# FIT_TCM_SI5338A.net
KiCad netlist of a schematic drawn in Altium Designer
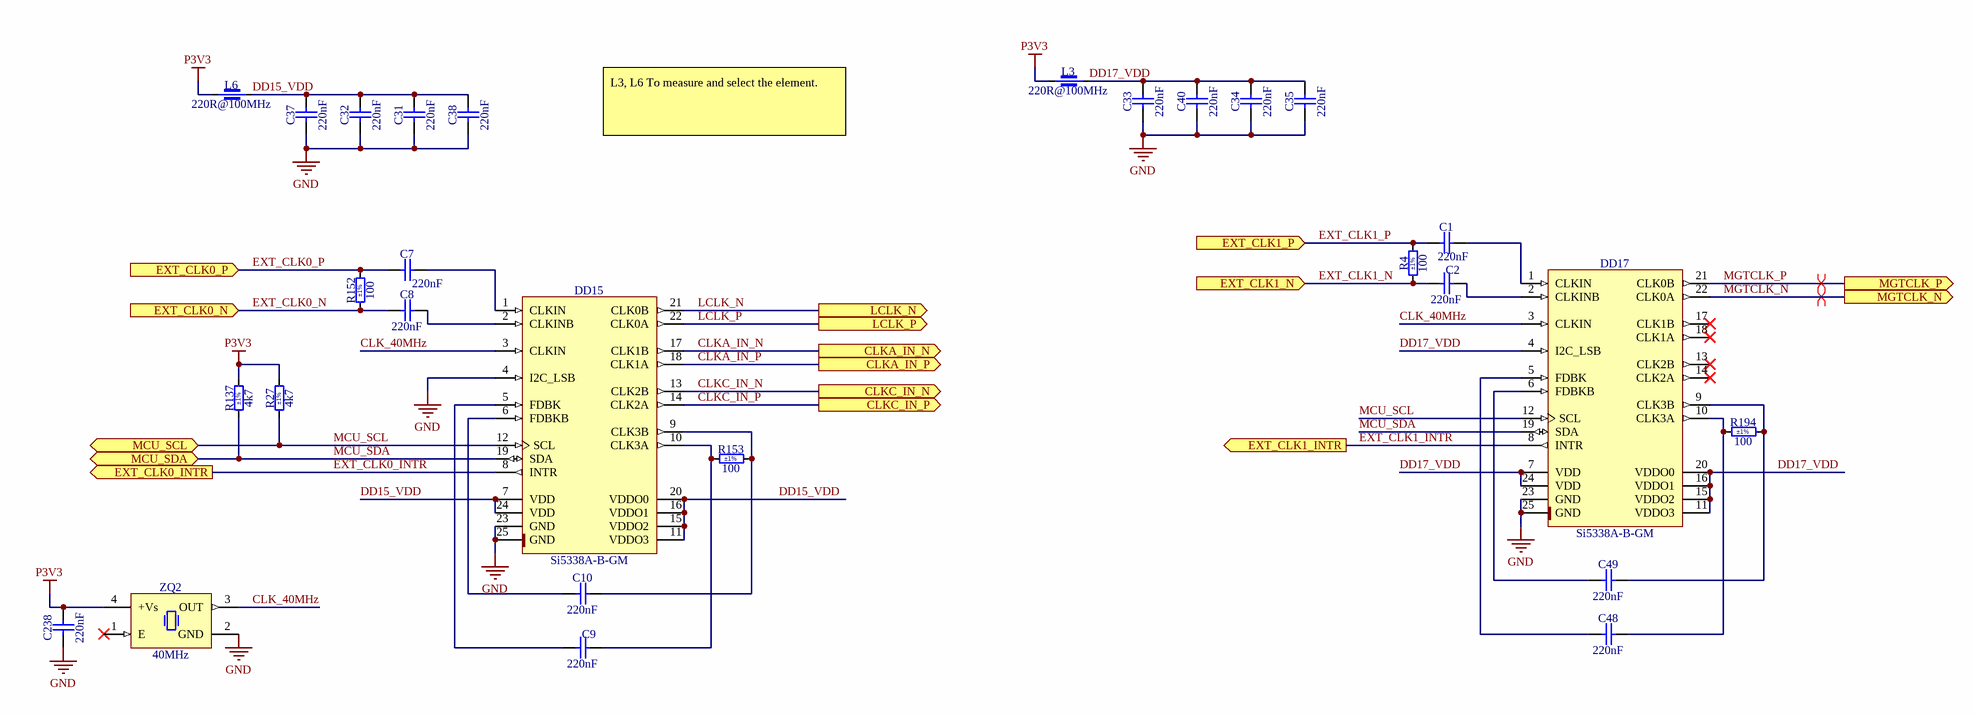
[diagram p0: FIT_TCM_SI5338A.SchDoc]

(export (version "E")
  (design (tool "Eeschema 10.0.6"))
  (components
    (comp (ref "C1")
      (value "220nF")
      (footprint "CAPC1608X87N")
      (description "Non-polarised capacitor")
      (fields
        (field (name "PART NUMBER") "CC0603_220NF_25V_10%_X7R")
        (field (name "VOLTAGE") "25V")
        (field (name "AUTHOR") "CERN DEM JLC")
      )
      (libsource (lib "Capacitors") (part "Capacitor - non polarized"))
    )
    (comp (ref "C2")
      (value "220nF")
      (footprint "CAPC1608X87N")
      (description "Non-polarised capacitor")
      (fields
        (field (name "PART NUMBER") "CC0603_220NF_25V_10%_X7R")
        (field (name "VOLTAGE") "25V")
        (field (name "AUTHOR") "CERN DEM JLC")
      )
      (libsource (lib "Capacitors") (part "Capacitor - non polarized"))
    )
    (comp (ref "C7")
      (value "220nF")
      (footprint "CAPC1608X87N")
      (description "Non-polarised capacitor")
      (fields
        (field (name "PART NUMBER") "CC0603_220NF_25V_10%_X7R")
        (field (name "VOLTAGE") "25V")
        (field (name "AUTHOR") "CERN DEM JLC")
      )
      (libsource (lib "Capacitors") (part "Capacitor - non polarized"))
    )
    (comp (ref "C8")
      (value "220nF")
      (footprint "CAPC1608X87N")
      (description "Non-polarised capacitor")
      (fields
        (field (name "PART NUMBER") "CC0603_220NF_25V_10%_X7R")
        (field (name "VOLTAGE") "25V")
        (field (name "AUTHOR") "CERN DEM JLC")
      )
      (libsource (lib "Capacitors") (part "Capacitor - non polarized"))
    )
    (comp (ref "C9")
      (value "220nF")
      (footprint "CAPC1608X87N")
      (description "Non-polarised capacitor")
      (fields
        (field (name "PART NUMBER") "CC0603_220NF_25V_10%_X7R")
        (field (name "VOLTAGE") "25V")
        (field (name "AUTHOR") "CERN DEM JLC")
      )
      (libsource (lib "Capacitors") (part "Capacitor - non polarized"))
    )
    (comp (ref "C10")
      (value "220nF")
      (footprint "CAPC1608X87N")
      (description "Non-polarised capacitor")
      (fields
        (field (name "PART NUMBER") "CC0603_220NF_25V_10%_X7R")
        (field (name "VOLTAGE") "25V")
        (field (name "AUTHOR") "CERN DEM JLC")
      )
      (libsource (lib "Capacitors") (part "Capacitor - non polarized"))
    )
    (comp (ref "C31")
      (value "220nF")
      (footprint "CAPC2012X135N")
      (description "Non-polarised capacitor")
      (fields
        (field (name "PART NUMBER") "CC0805_220NF_50V_10%_X7R")
        (field (name "VOLTAGE") "50V")
        (field (name "AUTHOR") "CERN DEM JLC")
      )
      (libsource (lib "Capacitors") (part "Capacitor - non polarized"))
    )
    (comp (ref "C32")
      (value "220nF")
      (footprint "CAPC2012X135N")
      (description "Non-polarised capacitor")
      (fields
        (field (name "PART NUMBER") "CC0805_220NF_50V_10%_X7R")
        (field (name "VOLTAGE") "50V")
        (field (name "AUTHOR") "CERN DEM JLC")
      )
      (libsource (lib "Capacitors") (part "Capacitor - non polarized"))
    )
    (comp (ref "C33")
      (value "220nF")
      (footprint "CAPC2012X135N")
      (description "Non-polarised capacitor")
      (fields
        (field (name "PART NUMBER") "CC0805_220NF_50V_10%_X7R")
        (field (name "VOLTAGE") "50V")
        (field (name "AUTHOR") "CERN DEM JLC")
      )
      (libsource (lib "Capacitors") (part "Capacitor - non polarized"))
    )
    (comp (ref "C34")
      (value "220nF")
      (footprint "CAPC2012X135N")
      (description "Non-polarised capacitor")
      (fields
        (field (name "PART NUMBER") "CC0805_220NF_50V_10%_X7R")
        (field (name "VOLTAGE") "50V")
        (field (name "AUTHOR") "CERN DEM JLC")
      )
      (libsource (lib "Capacitors") (part "Capacitor - non polarized"))
    )
    (comp (ref "C35")
      (value "220nF")
      (footprint "CAPC2012X135N")
      (description "Non-polarised capacitor")
      (fields
        (field (name "PART NUMBER") "CC0805_220NF_50V_10%_X7R")
        (field (name "VOLTAGE") "50V")
        (field (name "AUTHOR") "CERN DEM JLC")
      )
      (libsource (lib "Capacitors") (part "Capacitor - non polarized"))
    )
    (comp (ref "C37")
      (value "220nF")
      (footprint "CAPC2012X135N")
      (description "Non-polarised capacitor")
      (fields
        (field (name "PART NUMBER") "CC0805_220NF_50V_10%_X7R")
        (field (name "VOLTAGE") "50V")
        (field (name "AUTHOR") "CERN DEM JLC")
      )
      (libsource (lib "Capacitors") (part "Capacitor - non polarized"))
    )
    (comp (ref "C38")
      (value "220nF")
      (footprint "CAPC2012X135N")
      (description "Non-polarised capacitor")
      (fields
        (field (name "PART NUMBER") "CC0805_220NF_50V_10%_X7R")
        (field (name "VOLTAGE") "50V")
        (field (name "AUTHOR") "CERN DEM JLC")
      )
      (libsource (lib "Capacitors") (part "Capacitor - non polarized"))
    )
    (comp (ref "C40")
      (value "220nF")
      (footprint "CAPC2012X135N")
      (description "Non-polarised capacitor")
      (fields
        (field (name "PART NUMBER") "CC0805_220NF_50V_10%_X7R")
        (field (name "VOLTAGE") "50V")
        (field (name "AUTHOR") "CERN DEM JLC")
      )
      (libsource (lib "Capacitors") (part "Capacitor - non polarized"))
    )
    (comp (ref "C48")
      (value "220nF")
      (footprint "CAPC1608X87N")
      (description "Non-polarised capacitor")
      (fields
        (field (name "PART NUMBER") "CC0603_220NF_25V_10%_X7R")
        (field (name "VOLTAGE") "25V")
        (field (name "AUTHOR") "CERN DEM JLC")
      )
      (libsource (lib "Capacitors") (part "Capacitor - non polarized"))
    )
    (comp (ref "C49")
      (value "220nF")
      (footprint "CAPC1608X87N")
      (description "Non-polarised capacitor")
      (fields
        (field (name "PART NUMBER") "CC0603_220NF_25V_10%_X7R")
        (field (name "VOLTAGE") "25V")
        (field (name "AUTHOR") "CERN DEM JLC")
      )
      (libsource (lib "Capacitors") (part "Capacitor - non polarized"))
    )
    (comp (ref "C238")
      (value "220nF")
      (footprint "CAPC2012X135N")
      (description "Non-polarised capacitor")
      (fields
        (field (name "PART NUMBER") "CC0805_220NF_50V_10%_X7R")
        (field (name "VOLTAGE") "50V")
        (field (name "AUTHOR") "CERN DEM JLC")
      )
      (libsource (lib "Capacitors") (part "Capacitor - non polarized"))
    )
    (comp (ref "DD15")
      (value "Si5338A-B-GM")
      (footprint "QFN50P400X400X90-25N-S265")
      (description "I2C-Programmable Any-Frequency, Any-Output Quad Clock Generator")
      (fields (field (name "MANUFACTURER") "SILICON LABS") (field (name "AUTHOR") "CERN DEM JMW"))
      (libsource (lib "ICs And Semiconductors") (part "Si5338A"))
    )
    (comp (ref "DD17")
      (value "Si5338A-B-GM")
      (footprint "QFN50P400X400X90-25N-S265")
      (description "I2C-Programmable Any-Frequency, Any-Output Quad Clock Generator")
      (fields (field (name "MANUFACTURER") "SILICON LABS") (field (name "AUTHOR") "CERN DEM JMW"))
      (libsource (lib "ICs And Semiconductors") (part "Si5338A"))
    )
    (comp (ref "L3")
      (value "220R@100MHz")
      (footprint "INDC2012X105N")
      (fields
        (field (name "PART NUMBER") "IND0805_TDK_MPZ2012S221A")
        (field (name "POWER") "3A")
        (field (name "TOLERANCE") "±25%")
        (field (name "AUTHOR") "CERN DEM HF")
      )
      (libsource (lib "Inductors & Transformers") (part "Ferrite Bead"))
    )
    (comp (ref "L6")
      (value "220R@100MHz")
      (footprint "INDC2012X105N")
      (fields
        (field (name "PART NUMBER") "IND0805_TDK_MPZ2012S221A")
        (field (name "POWER") "3A")
        (field (name "TOLERANCE") "±25%")
        (field (name "AUTHOR") "CERN DEM HF")
      )
      (libsource (lib "Inductors & Transformers") (part "Ferrite Bead"))
    )
    (comp (ref "R4")
      (value "100")
      (footprint "RESC1608X55N")
      (description "Resistor - 1%")
      (fields
        (field (name "TOLERANCE") "±1%")
        (field (name "PART NUMBER") "R0603_100R_1%_0.1W_100PPM")
        (field (name "POWER") "0.1W")
        (field (name "AUTHOR") "CERN DEM JLC")
      )
      (libsource (lib "Resistors") (part "Resistor - 1%"))
    )
    (comp (ref "R27")
      (value "4k7")
      (footprint "RESC2012X60N")
      (description "Resistor - 1%")
      (fields
        (field (name "TOLERANCE") "±1%")
        (field (name "PART NUMBER") "R0805_4K7_1%_0.125W_100PPM")
        (field (name "POWER") "0.125W")
        (field (name "AUTHOR") "CERN DEM JLC")
      )
      (libsource (lib "Resistors") (part "Resistor - 1%"))
    )
    (comp (ref "R137")
      (value "4k7")
      (footprint "RESC2012X60N")
      (description "Resistor - 1%")
      (fields
        (field (name "TOLERANCE") "±1%")
        (field (name "PART NUMBER") "R0805_4K7_1%_0.125W_100PPM")
        (field (name "POWER") "0.125W")
        (field (name "AUTHOR") "CERN DEM JLC")
      )
      (libsource (lib "Resistors") (part "Resistor - 1%"))
    )
    (comp (ref "R152")
      (value "100")
      (footprint "RESC1608X55N")
      (description "Resistor - 1%")
      (fields
        (field (name "TOLERANCE") "±1%")
        (field (name "PART NUMBER") "R0603_100R_1%_0.1W_100PPM")
        (field (name "POWER") "0.1W")
        (field (name "AUTHOR") "CERN DEM JLC")
      )
      (libsource (lib "Resistors") (part "Resistor - 1%"))
    )
    (comp (ref "R153")
      (value "100")
      (footprint "RESC1608X55N")
      (description "Resistor - 1%")
      (fields
        (field (name "TOLERANCE") "±1%")
        (field (name "PART NUMBER") "R0603_100R_1%_0.1W_100PPM")
        (field (name "POWER") "0.1W")
        (field (name "AUTHOR") "CERN DEM JLC")
      )
      (libsource (lib "Resistors") (part "Resistor - 1%"))
    )
    (comp (ref "R194")
      (value "100")
      (footprint "RESC1608X55N")
      (description "Resistor - 1%")
      (fields
        (field (name "TOLERANCE") "±1%")
        (field (name "PART NUMBER") "R0603_100R_1%_0.1W_100PPM")
        (field (name "POWER") "0.1W")
        (field (name "AUTHOR") "CERN DEM JLC")
      )
      (libsource (lib "Resistors") (part "Resistor - 1%"))
    )
    (comp (ref "ZQ2")
      (value "40MHz")
      (footprint "OSC_IQD_CFPS-73")
      (description "Oscillator 4 pins 1=E 2=GND 3=OUT 4=+Vs")
      (fields
        (field (name "PART NUMBER") "OSC_40MHZ_IQD_LFSPXO018042")
        (field (name "MANUFACTURER") "IQD FREQUENCY PRODUCTS")
        (field (name "AUTHOR") "CERN DEM JLC")
      )
      (libsource (lib "ICs And Semiconductors") (part "Oscillator 1E 2GND 3OUT 4Vs"))
    )
  )
  (nets
    (net (code "1") (name "/CLKA_IN_N") (class "Default")
      (node (ref "DD15") (pin "17") (pinfunction "CLK1B_17") (pintype "output"))
    )
    (net (code "2") (name "/CLKA_IN_P") (class "Default")
      (node (ref "DD15") (pin "18") (pinfunction "CLK1A_18") (pintype "output"))
    )
    (net (code "3") (name "/CLKC_IN_N") (class "Default")
      (node (ref "DD15") (pin "13") (pinfunction "CLK2B_13") (pintype "output"))
    )
    (net (code "4") (name "/CLKC_IN_P") (class "Default")
      (node (ref "DD15") (pin "14") (pinfunction "CLK2A_14") (pintype "output"))
    )
    (net (code "5") (name "/CLK_40MHz") (class "Default")
      (node (ref "DD15") (pin "3") (pinfunction "CLKIN_3") (pintype "input"))
      (node (ref "DD17") (pin "3") (pinfunction "CLKIN_3") (pintype "input"))
      (node (ref "ZQ2") (pin "3") (pinfunction "OUT_3") (pintype "output"))
    )
    (net (code "6") (name "/DD15_VDD") (class "Default")
      (node (ref "C31") (pin "2") (pinfunction "2_2") (pintype "passive"))
      (node (ref "C32") (pin "2") (pinfunction "2_2") (pintype "passive"))
      (node (ref "C37") (pin "2") (pinfunction "2_2") (pintype "passive"))
      (node (ref "C38") (pin "2") (pinfunction "2_2") (pintype "passive"))
      (node (ref "DD15") (pin "11") (pinfunction "VDDO3_11") (pintype "power_in"))
      (node (ref "DD15") (pin "15") (pinfunction "VDDO2_15") (pintype "power_in"))
      (node (ref "DD15") (pin "16") (pinfunction "VDDO1_16") (pintype "power_in"))
      (node (ref "DD15") (pin "20") (pinfunction "VDDO0_20") (pintype "power_in"))
      (node (ref "DD15") (pin "24") (pinfunction "VDD_24") (pintype "power_in"))
      (node (ref "DD15") (pin "7") (pinfunction "VDD_7") (pintype "power_in"))
      (node (ref "L6") (pin "2") (pinfunction "2_2") (pintype "passive"))
    )
    (net (code "7") (name "/DD17_VDD") (class "Default")
      (node (ref "C33") (pin "2") (pinfunction "2_2") (pintype "passive"))
      (node (ref "C34") (pin "2") (pinfunction "2_2") (pintype "passive"))
      (node (ref "C35") (pin "2") (pinfunction "2_2") (pintype "passive"))
      (node (ref "C40") (pin "2") (pinfunction "2_2") (pintype "passive"))
      (node (ref "DD17") (pin "11") (pinfunction "VDDO3_11") (pintype "power_in"))
      (node (ref "DD17") (pin "15") (pinfunction "VDDO2_15") (pintype "power_in"))
      (node (ref "DD17") (pin "16") (pinfunction "VDDO1_16") (pintype "power_in"))
      (node (ref "DD17") (pin "20") (pinfunction "VDDO0_20") (pintype "power_in"))
      (node (ref "DD17") (pin "24") (pinfunction "VDD_24") (pintype "power_in"))
      (node (ref "DD17") (pin "4") (pinfunction "I2C_LSB_4") (pintype "input"))
      (node (ref "DD17") (pin "7") (pinfunction "VDD_7") (pintype "power_in"))
      (node (ref "L3") (pin "2") (pinfunction "2_2") (pintype "passive"))
    )
    (net (code "8") (name "/EXT_CLK0_INTR") (class "Default")
      (node (ref "DD15") (pin "8") (pinfunction "INTR_8") (pintype "output"))
    )
    (net (code "9") (name "/EXT_CLK0_N") (class "Default")
      (node (ref "C8") (pin "1") (pinfunction "1_1") (pintype "passive"))
      (node (ref "R152") (pin "1") (pinfunction "1_1") (pintype "passive"))
    )
    (net (code "10") (name "/EXT_CLK0_P") (class "Default")
      (node (ref "C7") (pin "1") (pinfunction "1_1") (pintype "passive"))
      (node (ref "R152") (pin "2") (pinfunction "2_2") (pintype "passive"))
    )
    (net (code "11") (name "/EXT_CLK1_INTR") (class "Default")
      (node (ref "DD17") (pin "8") (pinfunction "INTR_8") (pintype "output"))
    )
    (net (code "12") (name "/EXT_CLK1_N") (class "Default")
      (node (ref "C2") (pin "1") (pinfunction "1_1") (pintype "passive"))
      (node (ref "R4") (pin "1") (pinfunction "1_1") (pintype "passive"))
    )
    (net (code "13") (name "/EXT_CLK1_P") (class "Default")
      (node (ref "C1") (pin "1") (pinfunction "1_1") (pintype "passive"))
      (node (ref "R4") (pin "2") (pinfunction "2_2") (pintype "passive"))
    )
    (net (code "14") (name "/LCLK_N") (class "Default")
      (node (ref "DD15") (pin "21") (pinfunction "CLK0B_21") (pintype "output"))
    )
    (net (code "15") (name "/LCLK_P") (class "Default")
      (node (ref "DD15") (pin "22") (pinfunction "CLK0A_22") (pintype "output"))
    )
    (net (code "16") (name "/MCU_SCL") (class "Default")
      (node (ref "DD15") (pin "12") (pinfunction "SCL_12") (pintype "input"))
      (node (ref "DD17") (pin "12") (pinfunction "SCL_12") (pintype "input"))
      (node (ref "R27") (pin "1") (pinfunction "1_1") (pintype "passive"))
    )
    (net (code "17") (name "/MCU_SDA") (class "Default")
      (node (ref "DD15") (pin "19") (pinfunction "SDA_19") (pintype "bidirectional"))
      (node (ref "DD17") (pin "19") (pinfunction "SDA_19") (pintype "bidirectional"))
      (node (ref "R137") (pin "1") (pinfunction "1_1") (pintype "passive"))
    )
    (net (code "18") (name "/MGTCLK_N") (class "Default")
      (node (ref "DD17") (pin "22") (pinfunction "CLK0A_22") (pintype "output"))
    )
    (net (code "19") (name "/MGTCLK_P") (class "Default")
      (node (ref "DD17") (pin "21") (pinfunction "CLK0B_21") (pintype "output"))
    )
    (net (code "20") (name "GND") (class "Default")
      (node (ref "C238") (pin "1") (pinfunction "1_1") (pintype "passive"))
      (node (ref "C31") (pin "1") (pinfunction "1_1") (pintype "passive"))
      (node (ref "C32") (pin "1") (pinfunction "1_1") (pintype "passive"))
      (node (ref "C33") (pin "1") (pinfunction "1_1") (pintype "passive"))
      (node (ref "C34") (pin "1") (pinfunction "1_1") (pintype "passive"))
      (node (ref "C35") (pin "1") (pinfunction "1_1") (pintype "passive"))
      (node (ref "C37") (pin "1") (pinfunction "1_1") (pintype "passive"))
      (node (ref "C38") (pin "1") (pinfunction "1_1") (pintype "passive"))
      (node (ref "C40") (pin "1") (pinfunction "1_1") (pintype "passive"))
      (node (ref "DD15") (pin "23") (pinfunction "GND_23") (pintype "power_in"))
      (node (ref "DD15") (pin "25") (pinfunction "GND_25") (pintype "power_in"))
      (node (ref "DD15") (pin "4") (pinfunction "I2C_LSB_4") (pintype "input"))
      (node (ref "DD17") (pin "23") (pinfunction "GND_23") (pintype "power_in"))
      (node (ref "DD17") (pin "25") (pinfunction "GND_25") (pintype "power_in"))
      (node (ref "ZQ2") (pin "2") (pinfunction "GND_2") (pintype "power_in"))
    )
    (net (code "21") (name "Net-(C1-Pad2)") (class "Default")
      (node (ref "C1") (pin "2") (pinfunction "2_2") (pintype "passive"))
      (node (ref "DD17") (pin "1") (pinfunction "CLKIN_1") (pintype "input"))
    )
    (net (code "22") (name "Net-(C7-Pad2)") (class "Default")
      (node (ref "C7") (pin "2") (pinfunction "2_2") (pintype "passive"))
      (node (ref "DD15") (pin "1") (pinfunction "CLKIN_1") (pintype "input"))
    )
    (net (code "23") (name "Net-(DD15-CLK3A)") (class "Default")
      (node (ref "C9") (pin "2") (pinfunction "2_2") (pintype "passive"))
      (node (ref "DD15") (pin "10") (pinfunction "CLK3A_10") (pintype "output"))
      (node (ref "R153") (pin "1") (pinfunction "1_1") (pintype "passive"))
    )
    (net (code "24") (name "Net-(DD15-CLK3B)") (class "Default")
      (node (ref "C10") (pin "2") (pinfunction "2_2") (pintype "passive"))
      (node (ref "DD15") (pin "9") (pinfunction "CLK3B_9") (pintype "output"))
      (node (ref "R153") (pin "2") (pinfunction "2_2") (pintype "passive"))
    )
    (net (code "25") (name "Net-(DD15-CLKINB)") (class "Default")
      (node (ref "C8") (pin "2") (pinfunction "2_2") (pintype "passive"))
      (node (ref "DD15") (pin "2") (pinfunction "CLKINB_2") (pintype "input"))
    )
    (net (code "26") (name "Net-(DD15-FDBK)") (class "Default")
      (node (ref "C9") (pin "1") (pinfunction "1_1") (pintype "passive"))
      (node (ref "DD15") (pin "5") (pinfunction "FDBK_5") (pintype "input"))
    )
    (net (code "27") (name "Net-(DD15-FDBKB)") (class "Default")
      (node (ref "C10") (pin "1") (pinfunction "1_1") (pintype "passive"))
      (node (ref "DD15") (pin "6") (pinfunction "FDBKB_6") (pintype "input"))
    )
    (net (code "28") (name "Net-(DD17-CLK3A)") (class "Default")
      (node (ref "C48") (pin "2") (pinfunction "2_2") (pintype "passive"))
      (node (ref "DD17") (pin "10") (pinfunction "CLK3A_10") (pintype "output"))
      (node (ref "R194") (pin "1") (pinfunction "1_1") (pintype "passive"))
    )
    (net (code "29") (name "Net-(DD17-CLK3B)") (class "Default")
      (node (ref "C49") (pin "2") (pinfunction "2_2") (pintype "passive"))
      (node (ref "DD17") (pin "9") (pinfunction "CLK3B_9") (pintype "output"))
      (node (ref "R194") (pin "2") (pinfunction "2_2") (pintype "passive"))
    )
    (net (code "30") (name "Net-(DD17-CLKINB)") (class "Default")
      (node (ref "C2") (pin "2") (pinfunction "2_2") (pintype "passive"))
      (node (ref "DD17") (pin "2") (pinfunction "CLKINB_2") (pintype "input"))
    )
    (net (code "31") (name "Net-(DD17-FDBK)") (class "Default")
      (node (ref "C48") (pin "1") (pinfunction "1_1") (pintype "passive"))
      (node (ref "DD17") (pin "5") (pinfunction "FDBK_5") (pintype "input"))
    )
    (net (code "32") (name "Net-(DD17-FDBKB)") (class "Default")
      (node (ref "C49") (pin "1") (pinfunction "1_1") (pintype "passive"))
      (node (ref "DD17") (pin "6") (pinfunction "FDBKB_6") (pintype "input"))
    )
    (net (code "33") (name "P3V3") (class "Default")
      (node (ref "C238") (pin "2") (pinfunction "2_2") (pintype "passive"))
      (node (ref "L3") (pin "1") (pinfunction "1_1") (pintype "passive"))
      (node (ref "L6") (pin "1") (pinfunction "1_1") (pintype "passive"))
      (node (ref "R137") (pin "2") (pinfunction "2_2") (pintype "passive"))
      (node (ref "R27") (pin "2") (pinfunction "2_2") (pintype "passive"))
      (node (ref "ZQ2") (pin "4") (pinfunction "+Vs_4") (pintype "power_in"))
    )
    (net (code "34") (name "unconnected-(DD17-CLK1A-Pad18)") (class "Default")
      (node (ref "DD17") (pin "18") (pinfunction "CLK1A_18") (pintype "output+no_connect"))
    )
    (net (code "35") (name "unconnected-(DD17-CLK1B-Pad17)") (class "Default")
      (node (ref "DD17") (pin "17") (pinfunction "CLK1B_17") (pintype "output+no_connect"))
    )
    (net (code "36") (name "unconnected-(DD17-CLK2A-Pad14)") (class "Default")
      (node (ref "DD17") (pin "14") (pinfunction "CLK2A_14") (pintype "output+no_connect"))
    )
    (net (code "37") (name "unconnected-(DD17-CLK2B-Pad13)") (class "Default")
      (node (ref "DD17") (pin "13") (pinfunction "CLK2B_13") (pintype "output+no_connect"))
    )
    (net (code "38") (name "unconnected-(ZQ2-E-Pad1)") (class "Default")
      (node (ref "ZQ2") (pin "1") (pinfunction "E_1") (pintype "input+no_connect"))
    )
  )
)
